# SCH_humidity_esp32_2023-06-02.net
KiCad netlist of a schematic drawn in EasyEDA
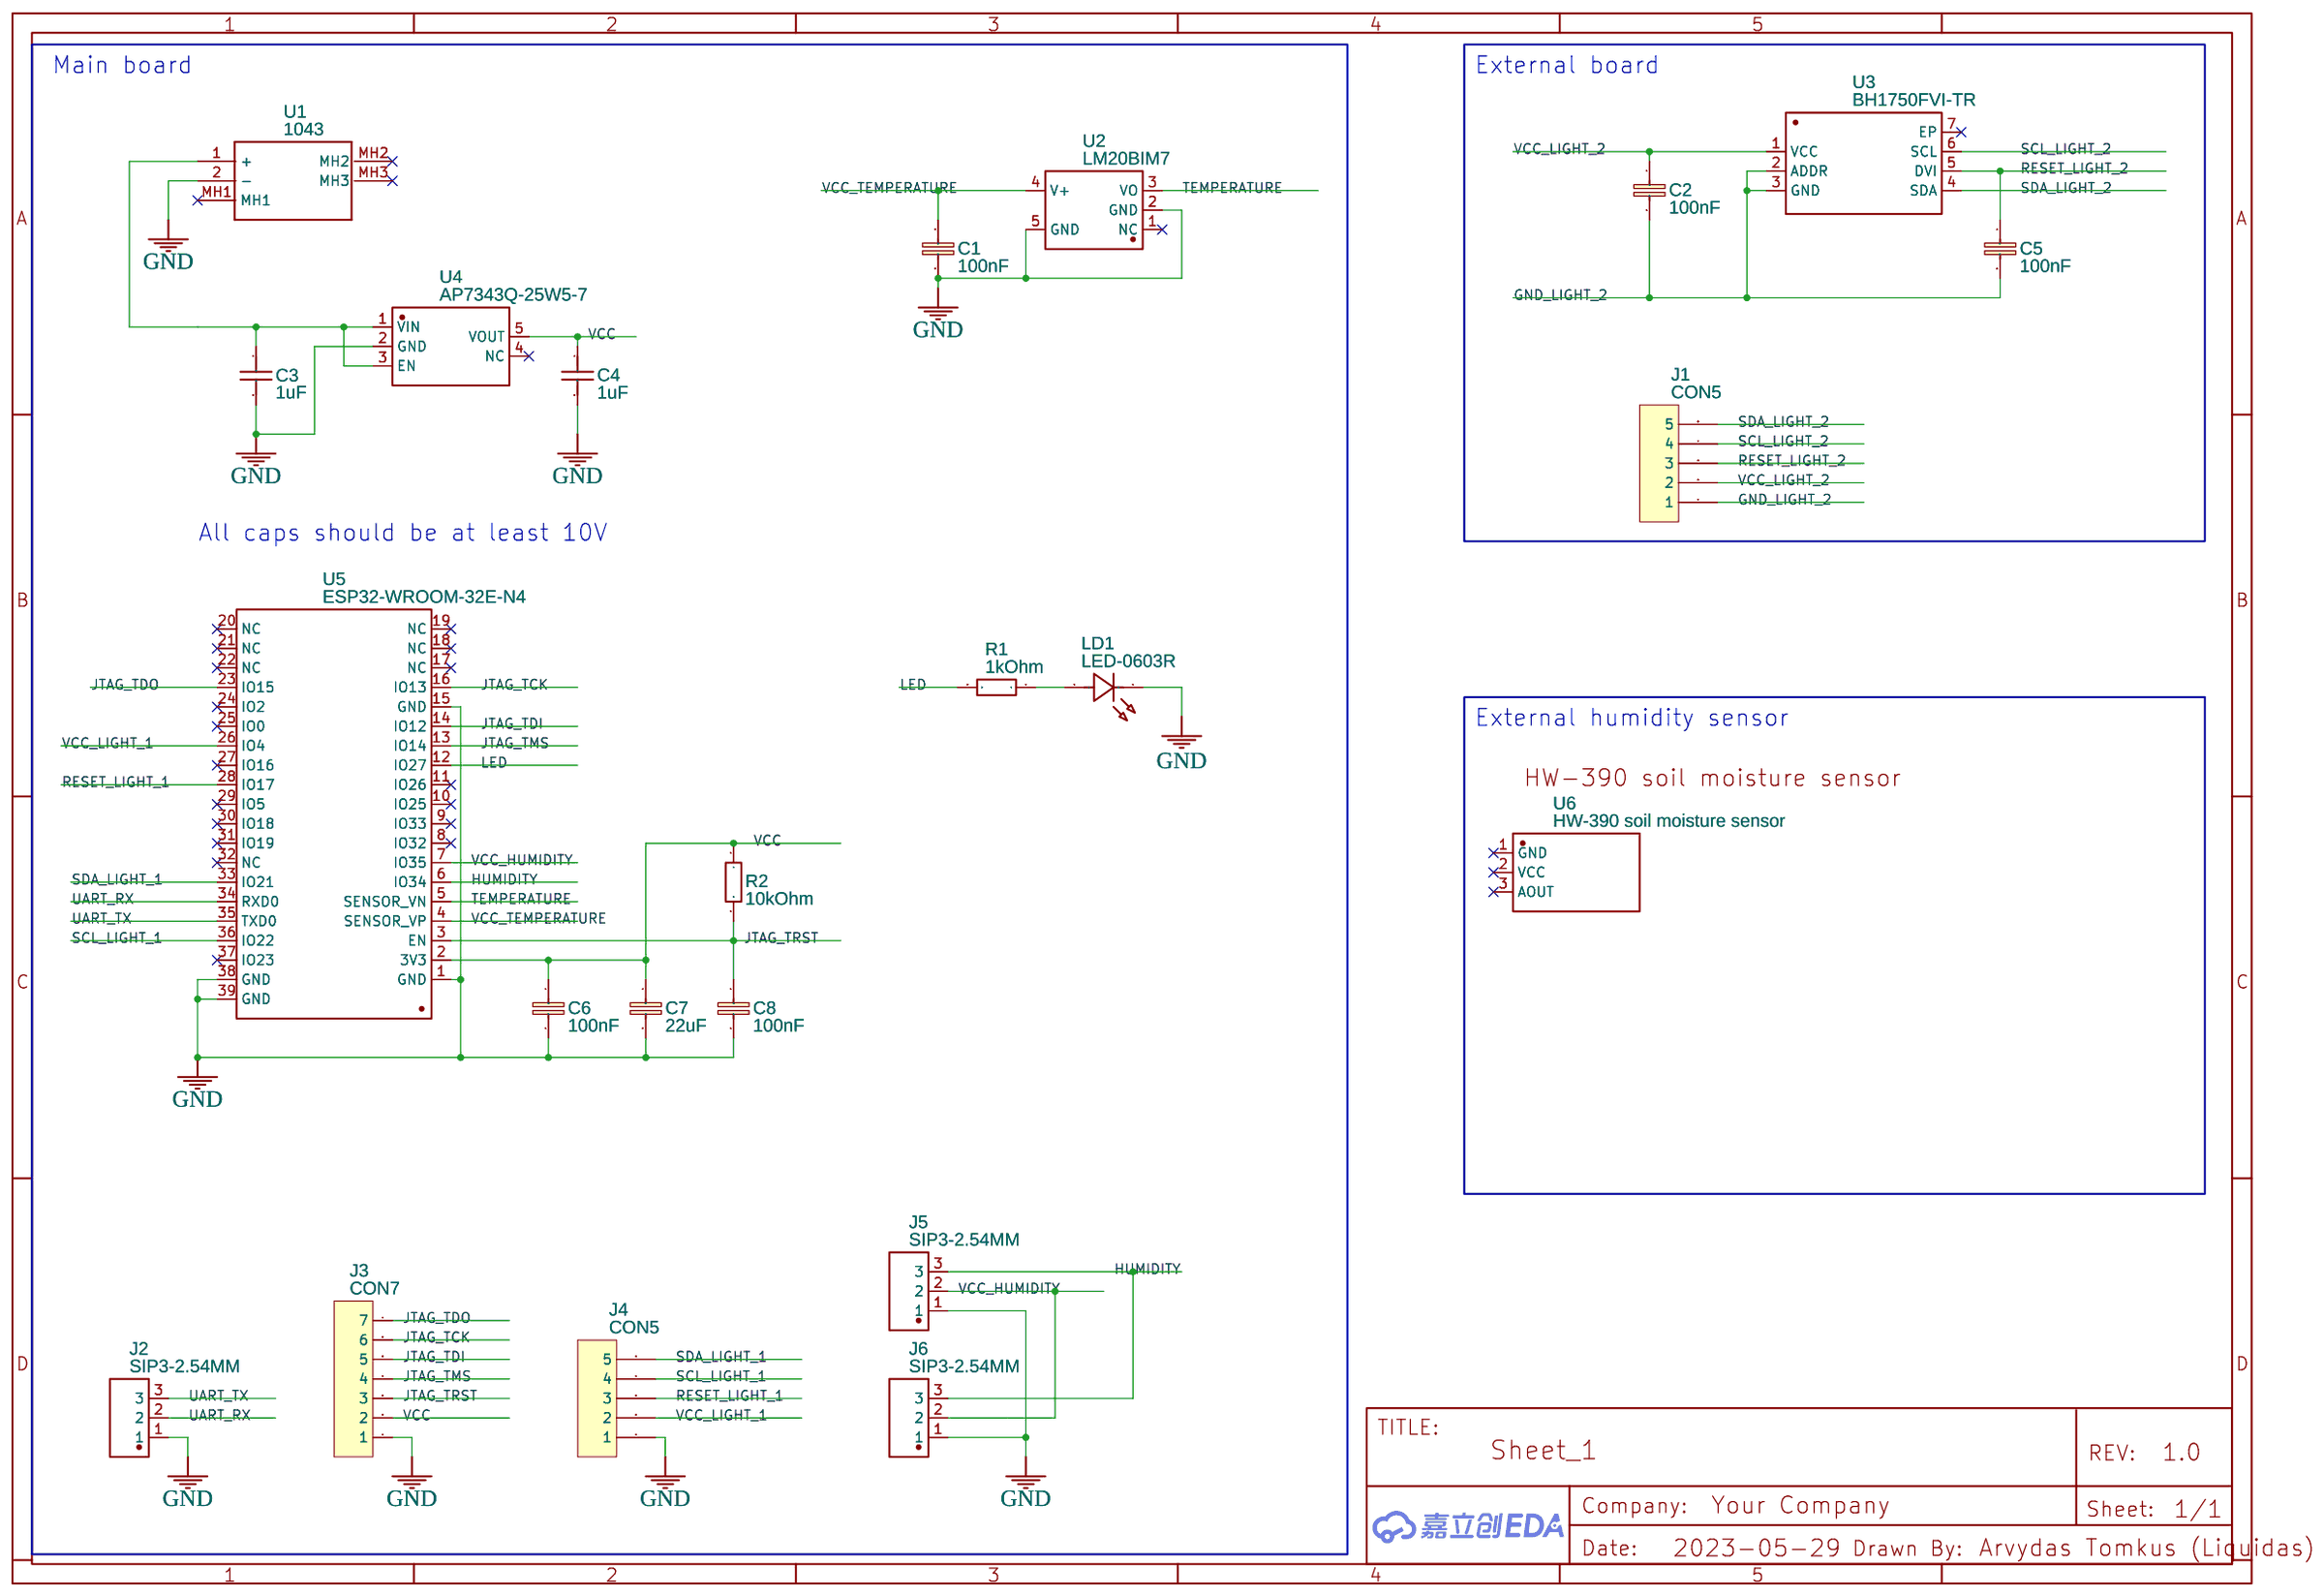
[diagram p0: schematic sheet]

(export (version "E")
  (design (tool "Eeschema 10.0.6"))
  (components
    (comp (ref "C1")
      (value "100nF")
      (fields (field (name "BOM_Manufacturer Part") "C0603C104K4RAC7867"))
      (libsource (lib "") (part "SPARKFUN-CAPACITORS_CAP0603-CAP"))
    )
    (comp (ref "C2")
      (value "100nF")
      (fields (field (name "BOM_Manufacturer Part") "C0603C104K4RAC7867"))
      (libsource (lib "") (part "SPARKFUN-CAPACITORS_CAP0603-CAP"))
    )
    (comp (ref "C3")
      (value "1uF")
      (fields (field (name "BOM_Manufacturer Part") "T491A105K010AT"))
      (libsource (lib "") (part "Capacitor SMD 1206"))
    )
    (comp (ref "C4")
      (value "1uF")
      (fields (field (name "BOM_Manufacturer Part") "T491A105K010AT"))
      (libsource (lib "") (part "Capacitor SMD 1206"))
    )
    (comp (ref "C5")
      (value "100nF")
      (fields (field (name "BOM_Manufacturer Part") "C0603C104K4RAC7867"))
      (libsource (lib "") (part "SPARKFUN-CAPACITORS_CAP0603-CAP"))
    )
    (comp (ref "C6")
      (value "100nF")
      (fields (field (name "BOM_Manufacturer Part") "C0603C104K4RAC7867"))
      (libsource (lib "") (part "SPARKFUN-CAPACITORS_CAP0603-CAP"))
    )
    (comp (ref "C7")
      (value "22uF")
      (fields (field (name "BOM_Manufacturer Part") "C0603C104K4RAC7867"))
      (libsource (lib "") (part "SPARKFUN-CAPACITORS_CAP0603-CAP"))
    )
    (comp (ref "C8")
      (value "100nF")
      (fields (field (name "BOM_Manufacturer Part") "C0603C104K4RAC7867"))
      (libsource (lib "") (part "SPARKFUN-CAPACITORS_CAP0603-CAP"))
    )
    (comp (ref "J1") (value "CON5") (libsource (lib "") (part "CON5")))
    (comp (ref "J2")
      (value "SIP3-2.54MM")
      (fields
        (field (name "BOM_Manufacturer Part") "SIP5-2.54mm")
        (field (name "BOM_Supplier Part") "C9900009053")
      )
      (libsource (lib "") (part "SIP3-2.54MM"))
    )
    (comp (ref "J3") (value "CON7") (libsource (lib "") (part "CON7")))
    (comp (ref "J4") (value "CON5") (libsource (lib "") (part "CON5")))
    (comp (ref "J5")
      (value "SIP3-2.54MM")
      (fields
        (field (name "BOM_Manufacturer Part") "SIP5-2.54mm")
        (field (name "BOM_Supplier Part") "C9900009053")
      )
      (libsource (lib "") (part "SIP3-2.54MM"))
    )
    (comp (ref "J6")
      (value "SIP3-2.54MM")
      (fields
        (field (name "BOM_Manufacturer Part") "SIP5-2.54mm")
        (field (name "BOM_Supplier Part") "C9900009053")
      )
      (libsource (lib "") (part "SIP3-2.54MM"))
    )
    (comp (ref "LD1")
      (value "LED-0603R")
      (fields (field (name "BOM_Manufacturer Part") "150060RS75000"))
      (libsource (lib "") (part "LED-0603R"))
    )
    (comp (ref "R1")
      (value "1kOhm")
      (fields
        (field (name "BOM_Manufacturer Part") "1K-R0603")
        (field (name "BOM_Supplier Part") "C9900009267")
      )
      (libsource (lib "") (part "1K-R0603_1"))
    )
    (comp (ref "R2")
      (value "10kOhm")
      (fields
        (field (name "BOM_Manufacturer Part") "1K-R0603")
        (field (name "BOM_Supplier Part") "C9900009267")
      )
      (libsource (lib "") (part "1K-R0603"))
    )
    (comp (ref "U1") (value "1043") (libsource (lib "") (part "1043")))
    (comp (ref "U2") (value "LM20BIM7") (libsource (lib "") (part "LM20BIM7")))
    (comp (ref "U3")
      (value "BH1750FVI-TR")
      (fields (field (name "BOM_Supplier Part") "C78960"))
      (libsource (lib "") (part "BH1750FVI-TR"))
    )
    (comp (ref "U4")
      (value "AP7343Q-25W5-7")
      (fields (field (name "BOM_Manufacturer Part") "AP7343-12W5-7"))
      (libsource (lib "") (part "AP7343-12W5-7"))
    )
    (comp (ref "U5") (value "ESP32-WROOM-32E-N4") (libsource (lib "") (part "ESP32-WROOM-32E-N4")))
    (comp (ref "U6")
      (value "HW-390 soil moisture sensor")
      (libsource (lib "") (part "HW-390 soil moisture sensor"))
    )
  )
  (nets
    (net (code "1") (name "/GND_LIGHT_2") (class "Default")
      (node (ref "C2") (pin "2") (pinfunction "2_2") (pintype "bidirectional"))
      (node (ref "C5") (pin "2") (pinfunction "2_2") (pintype "bidirectional"))
      (node (ref "J1") (pin "1") (pinfunction "1_1") (pintype "unspecified"))
      (node (ref "U3") (pin "2") (pinfunction "ADDR_2") (pintype "unspecified"))
      (node (ref "U3") (pin "3") (pinfunction "GND_3") (pintype "unspecified"))
    )
    (net (code "2") (name "/HUMIDITY") (class "Default")
      (node (ref "J5") (pin "3") (pinfunction "3_3") (pintype "unspecified"))
      (node (ref "J6") (pin "3") (pinfunction "3_3") (pintype "unspecified"))
      (node (ref "U5") (pin "6") (pinfunction "IO34_6") (pintype "unspecified"))
    )
    (net (code "3") (name "/JTAG_TCK") (class "Default")
      (node (ref "J3") (pin "6") (pinfunction "6_6") (pintype "unspecified"))
      (node (ref "U5") (pin "16") (pinfunction "IO13_16") (pintype "unspecified"))
    )
    (net (code "4") (name "/JTAG_TDI") (class "Default")
      (node (ref "J3") (pin "5") (pinfunction "5_5") (pintype "unspecified"))
      (node (ref "U5") (pin "14") (pinfunction "IO12_14") (pintype "unspecified"))
    )
    (net (code "5") (name "/JTAG_TDO") (class "Default")
      (node (ref "J3") (pin "7") (pinfunction "7_7") (pintype "unspecified"))
      (node (ref "U5") (pin "23") (pinfunction "IO15_23") (pintype "unspecified"))
    )
    (net (code "6") (name "/JTAG_TMS") (class "Default")
      (node (ref "J3") (pin "4") (pinfunction "4_4") (pintype "unspecified"))
      (node (ref "U5") (pin "13") (pinfunction "IO14_13") (pintype "unspecified"))
    )
    (net (code "7") (name "/JTAG_TRST") (class "Default")
      (node (ref "C8") (pin "1") (pinfunction "1_1") (pintype "bidirectional"))
      (node (ref "J3") (pin "3") (pinfunction "3_3") (pintype "unspecified"))
      (node (ref "R2") (pin "2") (pinfunction "2_2") (pintype "unspecified"))
      (node (ref "U5") (pin "3") (pinfunction "EN_3") (pintype "unspecified"))
    )
    (net (code "8") (name "/LED") (class "Default")
      (node (ref "R1") (pin "2") (pinfunction "2_2") (pintype "unspecified"))
      (node (ref "U5") (pin "12") (pinfunction "IO27_12") (pintype "unspecified"))
    )
    (net (code "9") (name "/RESET_LIGHT_1") (class "Default")
      (node (ref "J4") (pin "3") (pinfunction "3_3") (pintype "unspecified"))
      (node (ref "U5") (pin "28") (pinfunction "IO17_28") (pintype "unspecified"))
    )
    (net (code "10") (name "/RESET_LIGHT_2") (class "Default")
      (node (ref "C5") (pin "1") (pinfunction "1_1") (pintype "bidirectional"))
      (node (ref "J1") (pin "3") (pinfunction "3_3") (pintype "unspecified"))
      (node (ref "U3") (pin "5") (pinfunction "DVI_5") (pintype "unspecified"))
    )
    (net (code "11") (name "/SCL_LIGHT_1") (class "Default")
      (node (ref "J4") (pin "4") (pinfunction "4_4") (pintype "unspecified"))
      (node (ref "U5") (pin "36") (pinfunction "IO22_36") (pintype "unspecified"))
    )
    (net (code "12") (name "/SCL_LIGHT_2") (class "Default")
      (node (ref "J1") (pin "4") (pinfunction "4_4") (pintype "unspecified"))
      (node (ref "U3") (pin "6") (pinfunction "SCL_6") (pintype "unspecified"))
    )
    (net (code "13") (name "/SDA_LIGHT_1") (class "Default")
      (node (ref "J4") (pin "5") (pinfunction "5_5") (pintype "unspecified"))
      (node (ref "U5") (pin "33") (pinfunction "IO21_33") (pintype "unspecified"))
    )
    (net (code "14") (name "/SDA_LIGHT_2") (class "Default")
      (node (ref "J1") (pin "5") (pinfunction "5_5") (pintype "unspecified"))
      (node (ref "U3") (pin "4") (pinfunction "SDA_4") (pintype "unspecified"))
    )
    (net (code "15") (name "/TEMPERATURE") (class "Default")
      (node (ref "U2") (pin "3") (pinfunction "VO_3") (pintype "unspecified"))
      (node (ref "U5") (pin "5") (pinfunction "SENSOR_VN_5") (pintype "unspecified"))
    )
    (net (code "16") (name "/UART_RX") (class "Default")
      (node (ref "J2") (pin "2") (pinfunction "2_2") (pintype "unspecified"))
      (node (ref "U5") (pin "34") (pinfunction "RXD0_34") (pintype "unspecified"))
    )
    (net (code "17") (name "/UART_TX") (class "Default")
      (node (ref "J2") (pin "3") (pinfunction "3_3") (pintype "unspecified"))
      (node (ref "U5") (pin "35") (pinfunction "TXD0_35") (pintype "unspecified"))
    )
    (net (code "18") (name "/VCC") (class "Default")
      (node (ref "C4") (pin "1") (pinfunction "1_1") (pintype "unspecified"))
      (node (ref "C6") (pin "1") (pinfunction "1_1") (pintype "bidirectional"))
      (node (ref "C7") (pin "1") (pinfunction "1_1") (pintype "bidirectional"))
      (node (ref "J3") (pin "2") (pinfunction "2_2") (pintype "unspecified"))
      (node (ref "R2") (pin "1") (pinfunction "1_1") (pintype "unspecified"))
      (node (ref "U4") (pin "5") (pinfunction "VOUT_5") (pintype "unspecified"))
      (node (ref "U5") (pin "2") (pinfunction "3V3_2") (pintype "unspecified"))
    )
    (net (code "19") (name "/VCC_HUMIDITY") (class "Default")
      (node (ref "J5") (pin "2") (pinfunction "2_2") (pintype "unspecified"))
      (node (ref "J6") (pin "2") (pinfunction "2_2") (pintype "unspecified"))
      (node (ref "U5") (pin "7") (pinfunction "IO35_7") (pintype "unspecified"))
    )
    (net (code "20") (name "/VCC_LIGHT_1") (class "Default")
      (node (ref "J4") (pin "2") (pinfunction "2_2") (pintype "unspecified"))
      (node (ref "U5") (pin "26") (pinfunction "IO4_26") (pintype "unspecified"))
    )
    (net (code "21") (name "/VCC_LIGHT_2") (class "Default")
      (node (ref "C2") (pin "1") (pinfunction "1_1") (pintype "bidirectional"))
      (node (ref "J1") (pin "2") (pinfunction "2_2") (pintype "unspecified"))
      (node (ref "U3") (pin "1") (pinfunction "VCC_1") (pintype "unspecified"))
    )
    (net (code "22") (name "/VCC_TEMPERATURE") (class "Default")
      (node (ref "C1") (pin "1") (pinfunction "1_1") (pintype "bidirectional"))
      (node (ref "U2") (pin "4") (pinfunction "V+_4") (pintype "unspecified"))
      (node (ref "U5") (pin "4") (pinfunction "SENSOR_VP_4") (pintype "unspecified"))
    )
    (net (code "23") (name "GND") (class "Default")
      (node (ref "C1") (pin "2") (pinfunction "2_2") (pintype "bidirectional"))
      (node (ref "C3") (pin "2") (pinfunction "2_2") (pintype "unspecified"))
      (node (ref "C4") (pin "2") (pinfunction "2_2") (pintype "unspecified"))
      (node (ref "C6") (pin "2") (pinfunction "2_2") (pintype "bidirectional"))
      (node (ref "C7") (pin "2") (pinfunction "2_2") (pintype "bidirectional"))
      (node (ref "C8") (pin "2") (pinfunction "2_2") (pintype "bidirectional"))
      (node (ref "J2") (pin "1") (pinfunction "1_1") (pintype "unspecified"))
      (node (ref "J3") (pin "1") (pinfunction "1_1") (pintype "unspecified"))
      (node (ref "J4") (pin "1") (pinfunction "1_1") (pintype "unspecified"))
      (node (ref "J5") (pin "1") (pinfunction "1_1") (pintype "unspecified"))
      (node (ref "J6") (pin "1") (pinfunction "1_1") (pintype "unspecified"))
      (node (ref "LD1") (pin "1") (pinfunction "K_1") (pintype "unspecified"))
      (node (ref "U1") (pin "2") (pinfunction "-_2") (pintype "bidirectional"))
      (node (ref "U2") (pin "2") (pinfunction "GND_2") (pintype "unspecified"))
      (node (ref "U2") (pin "5") (pinfunction "GND_5") (pintype "unspecified"))
      (node (ref "U4") (pin "2") (pinfunction "GND_2") (pintype "unspecified"))
      (node (ref "U5") (pin "1") (pinfunction "GND_1") (pintype "unspecified"))
      (node (ref "U5") (pin "15") (pinfunction "GND_15") (pintype "unspecified"))
      (node (ref "U5") (pin "38") (pinfunction "GND_38") (pintype "unspecified"))
      (node (ref "U5") (pin "39") (pinfunction "GND_39") (pintype "unspecified"))
    )
    (net (code "24") (name "Net-(LD1-A)") (class "Default")
      (node (ref "LD1") (pin "2") (pinfunction "A_2") (pintype "unspecified"))
      (node (ref "R1") (pin "1") (pinfunction "1_1") (pintype "unspecified"))
    )
    (net (code "25") (name "Net-(U1-+)") (class "Default")
      (node (ref "C3") (pin "1") (pinfunction "1_1") (pintype "unspecified"))
      (node (ref "U1") (pin "1") (pinfunction "+_1") (pintype "bidirectional"))
      (node (ref "U4") (pin "1") (pinfunction "VIN_1") (pintype "unspecified"))
      (node (ref "U4") (pin "3") (pinfunction "EN_3") (pintype "unspecified"))
    )
    (net (code "26") (name "unconnected-(U1-PadMH1)") (class "Default")
      (node (ref "U1") (pin "MH1") (pinfunction "MH1_MH1") (pintype "bidirectional+no_connect"))
    )
    (net (code "27") (name "unconnected-(U1-PadMH2)") (class "Default")
      (node (ref "U1") (pin "MH2") (pinfunction "MH2_MH2") (pintype "bidirectional+no_connect"))
    )
    (net (code "28") (name "unconnected-(U1-PadMH3)") (class "Default")
      (node (ref "U1") (pin "MH3") (pinfunction "MH3_MH3") (pintype "bidirectional+no_connect"))
    )
    (net (code "29") (name "unconnected-(U2-NC-Pad1)") (class "Default")
      (node (ref "U2") (pin "1") (pinfunction "NC_1") (pintype "unspecified+no_connect"))
    )
    (net (code "30") (name "unconnected-(U3-EP-Pad7)") (class "Default")
      (node (ref "U3") (pin "7") (pinfunction "EP_7") (pintype "unspecified+no_connect"))
    )
    (net (code "31") (name "unconnected-(U4-NC-Pad4)") (class "Default")
      (node (ref "U4") (pin "4") (pinfunction "NC_4") (pintype "unspecified+no_connect"))
    )
    (net (code "32") (name "unconnected-(U5-IO0-Pad25)") (class "Default")
      (node (ref "U5") (pin "25") (pinfunction "IO0_25") (pintype "unspecified+no_connect"))
    )
    (net (code "33") (name "unconnected-(U5-IO2-Pad24)") (class "Default")
      (node (ref "U5") (pin "24") (pinfunction "IO2_24") (pintype "unspecified+no_connect"))
    )
    (net (code "34") (name "unconnected-(U5-IO5-Pad29)") (class "Default")
      (node (ref "U5") (pin "29") (pinfunction "IO5_29") (pintype "unspecified+no_connect"))
    )
    (net (code "35") (name "unconnected-(U5-IO16-Pad27)") (class "Default")
      (node (ref "U5") (pin "27") (pinfunction "IO16_27") (pintype "unspecified+no_connect"))
    )
    (net (code "36") (name "unconnected-(U5-IO18-Pad30)") (class "Default")
      (node (ref "U5") (pin "30") (pinfunction "IO18_30") (pintype "unspecified+no_connect"))
    )
    (net (code "37") (name "unconnected-(U5-IO19-Pad31)") (class "Default")
      (node (ref "U5") (pin "31") (pinfunction "IO19_31") (pintype "unspecified+no_connect"))
    )
    (net (code "38") (name "unconnected-(U5-IO23-Pad37)") (class "Default")
      (node (ref "U5") (pin "37") (pinfunction "IO23_37") (pintype "unspecified+no_connect"))
    )
    (net (code "39") (name "unconnected-(U5-IO25-Pad10)") (class "Default")
      (node (ref "U5") (pin "10") (pinfunction "IO25_10") (pintype "unspecified+no_connect"))
    )
    (net (code "40") (name "unconnected-(U5-IO26-Pad11)") (class "Default")
      (node (ref "U5") (pin "11") (pinfunction "IO26_11") (pintype "unspecified+no_connect"))
    )
    (net (code "41") (name "unconnected-(U5-IO32-Pad8)") (class "Default")
      (node (ref "U5") (pin "8") (pinfunction "IO32_8") (pintype "unspecified+no_connect"))
    )
    (net (code "42") (name "unconnected-(U5-IO33-Pad9)") (class "Default")
      (node (ref "U5") (pin "9") (pinfunction "IO33_9") (pintype "unspecified+no_connect"))
    )
    (net (code "43") (name "unconnected-(U5-NC-Pad17)") (class "Default")
      (node (ref "U5") (pin "17") (pinfunction "NC_17") (pintype "unspecified+no_connect"))
    )
    (net (code "44") (name "unconnected-(U5-NC-Pad18)") (class "Default")
      (node (ref "U5") (pin "18") (pinfunction "NC_18") (pintype "unspecified+no_connect"))
    )
    (net (code "45") (name "unconnected-(U5-NC-Pad19)") (class "Default")
      (node (ref "U5") (pin "19") (pinfunction "NC_19") (pintype "unspecified+no_connect"))
    )
    (net (code "46") (name "unconnected-(U5-NC-Pad20)") (class "Default")
      (node (ref "U5") (pin "20") (pinfunction "NC_20") (pintype "unspecified+no_connect"))
    )
    (net (code "47") (name "unconnected-(U5-NC-Pad21)") (class "Default")
      (node (ref "U5") (pin "21") (pinfunction "NC_21") (pintype "unspecified+no_connect"))
    )
    (net (code "48") (name "unconnected-(U5-NC-Pad22)") (class "Default")
      (node (ref "U5") (pin "22") (pinfunction "NC_22") (pintype "unspecified+no_connect"))
    )
    (net (code "49") (name "unconnected-(U5-NC-Pad32)") (class "Default")
      (node (ref "U5") (pin "32") (pinfunction "NC_32") (pintype "unspecified+no_connect"))
    )
    (net (code "50") (name "unconnected-(U6-AOUT-Pad3)") (class "Default")
      (node (ref "U6") (pin "3") (pinfunction "AOUT_3") (pintype "unspecified+no_connect"))
    )
    (net (code "51") (name "unconnected-(U6-GND-Pad1)") (class "Default")
      (node (ref "U6") (pin "1") (pinfunction "GND_1") (pintype "unspecified+no_connect"))
    )
    (net (code "52") (name "unconnected-(U6-VCC-Pad2)") (class "Default")
      (node (ref "U6") (pin "2") (pinfunction "VCC_2") (pintype "unspecified+no_connect"))
    )
  )
)
